# eMMC.net
KiCad netlist of a schematic drawn in Altium Designer
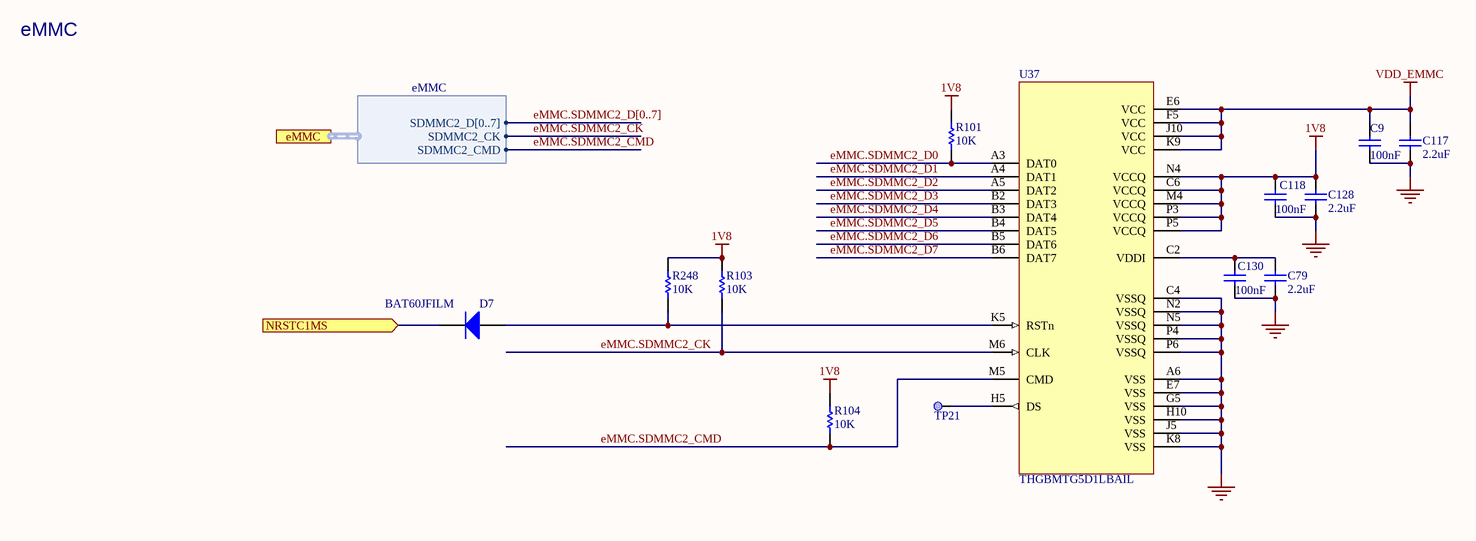
[diagram p0: eMMC.SchDoc]

(export (version "E")
  (design (tool "Eeschema 10.0.6"))
  (components
    (comp (ref "C9")
      (value "100nF")
      (footprint "C0402")
      (description "Capacitor, MLCC, 100nF, 16V, X7R, +/-10%, 0402, T=0.5mm")
      (fields (field (name "INTERNAL_PART_NUMBER") "MCD-00006") (field (name "MANUFACTURER") "YAGEO"))
      (libsource (lib "MCD_PARTS_database") (part "Capacitor"))
    )
    (comp (ref "C79")
      (value "2.2uF")
      (footprint "C0402")
      (description "Capacitor, MLCC, 2.2uF, 6.3V, X5R, +/-10%, 0402, T=0.5mm")
      (fields (field (name "INTERNAL_PART_NUMBER") "MCD-02606") (field (name "MANUFACTURER") "YAGEO"))
      (libsource (lib "MCD_PARTS_database") (part "Capacitor"))
    )
    (comp (ref "C117")
      (value "2.2uF")
      (footprint "C0402")
      (description "Capacitor, MLCC, 2.2uF, 6.3V, X5R, +/-10%, 0402, T=0.5mm")
      (fields (field (name "INTERNAL_PART_NUMBER") "MCD-02606") (field (name "MANUFACTURER") "YAGEO"))
      (libsource (lib "MCD_PARTS_database") (part "Capacitor"))
    )
    (comp (ref "C118")
      (value "100nF")
      (footprint "C0402")
      (description "Capacitor, MLCC, 100nF, 16V, X7R, +/-10%, 0402, T=0.5mm")
      (fields (field (name "INTERNAL_PART_NUMBER") "MCD-00006") (field (name "MANUFACTURER") "YAGEO"))
      (libsource (lib "MCD_PARTS_database") (part "Capacitor"))
    )
    (comp (ref "C128")
      (value "2.2uF")
      (footprint "C0402")
      (description "Capacitor, MLCC, 2.2uF, 6.3V, X5R, +/-10%, 0402, T=0.5mm")
      (fields (field (name "INTERNAL_PART_NUMBER") "MCD-02606") (field (name "MANUFACTURER") "YAGEO"))
      (libsource (lib "MCD_PARTS_database") (part "Capacitor"))
    )
    (comp (ref "C130")
      (value "100nF")
      (footprint "C0402")
      (description "Capacitor, MLCC, 100nF, 16V, X7R, +/-10%, 0402, T=0.5mm")
      (fields (field (name "INTERNAL_PART_NUMBER") "MCD-00006") (field (name "MANUFACTURER") "YAGEO"))
      (libsource (lib "MCD_PARTS_database") (part "Capacitor"))
    )
    (comp (ref "D7")
      (value "BAT60JFILM")
      (footprint "DIO_SOD323")
      (fields
        (field (name "INTERNAL_PART_NUMBER") "MCD-00034")
        (field (name "BMS_PART_NUMBER") "9151097")
        (field (name "MANUFACTURER") "STMICROELECTRONICS")
      )
      (libsource (lib "MCD_PARTS_database") (part "BAT60JFILM"))
    )
    (comp (ref "R101")
      (value "10K")
      (footprint "R0402")
      (description "Resistor,10K,0402,1%,1/16W")
      (fields
        (field (name "INTERNAL_PART_NUMBER") "MCD-00053")
        (field (name "MANUFACTURER_PART_NUMBER") "RC0402FR-0710KL")
        (field (name "PROVIDED_BY") "SUBCO")
      )
      (libsource (lib "MCD_PARTS_database") (part "Resistor"))
    )
    (comp (ref "R103")
      (value "10K")
      (footprint "R0402")
      (description "Resistor,10K,0402,1%,1/16W")
      (fields
        (field (name "INTERNAL_PART_NUMBER") "MCD-00053")
        (field (name "MANUFACTURER_PART_NUMBER") "RC0402FR-0710KL")
        (field (name "PROVIDED_BY") "SUBCO")
      )
      (libsource (lib "MCD_PARTS_database") (part "Resistor"))
    )
    (comp (ref "R104")
      (value "10K")
      (footprint "R0402")
      (description "Resistor,10K,0402,1%,1/16W")
      (fields
        (field (name "INTERNAL_PART_NUMBER") "MCD-00053")
        (field (name "MANUFACTURER_PART_NUMBER") "RC0402FR-0710KL")
        (field (name "PROVIDED_BY") "SUBCO")
      )
      (libsource (lib "MCD_PARTS_database") (part "Resistor"))
    )
    (comp (ref "R248")
      (value "10K")
      (footprint "R0402")
      (description "Resistor,10K,0402,1%,1/16W")
      (fields
        (field (name "INTERNAL_PART_NUMBER") "MCD-00053")
        (field (name "MANUFACTURER_PART_NUMBER") "RC0402FR-0710KL")
        (field (name "PROVIDED_BY") "SUBCO")
      )
      (libsource (lib "MCD_PARTS_database") (part "Resistor"))
    )
    (comp (ref "TP21")
      (value "Test Point")
      (footprint "TP_SMD_1MM")
      (description "Test Point 1mm")
      (fields
        (field (name "INTERNAL_PART_NUMBER") "MCD-00074")
        (field (name "MANUFACTURER_PART_NUMBER") "n/a")
      )
      (libsource (lib "MCD_PARTS_database") (part "Test Point"))
    )
    (comp (ref "U37")
      (value "THGBMTG5D1LBAIL")
      (footprint "ICC_P-WFBGA153_13X11P5_P050")
      (description "Memory, eMMC, 4GB, 15nm ,WFBGA , 153 pins")
      (fields (field (name "INTERNAL_PART_NUMBER") "MCD-02799") (field (name "MANUFACTURER") "KIOXIA"))
      (libsource (lib "MCD_PARTS_database") (part "eMMC_THGBMTG5D1LBAIL"))
    )
  )
  (nets
    (net (code "2") (name "/NRSTC1MS") (class "Default")
      (node (ref "D7") (pin "2") (pinfunction "K_2") (pintype "passive"))
    )
    (net (code "3") (name "/eMMC.SDMMC2_CK") (class "Default")
      (node (ref "R103") (pin "1") (pinfunction "1_1") (pintype "passive"))
      (node (ref "U37") (pin "M6") (pinfunction "CLK_M6") (pintype "input"))
    )
    (net (code "4") (name "/eMMC.SDMMC2_CMD") (class "Default")
      (node (ref "R104") (pin "1") (pinfunction "1_1") (pintype "passive"))
      (node (ref "U37") (pin "M5") (pinfunction "CMD_M5") (pintype "passive"))
    )
    (net (code "5") (name "/eMMC.SDMMC2_D0") (class "Default")
      (node (ref "R101") (pin "1") (pinfunction "1_1") (pintype "passive"))
      (node (ref "U37") (pin "A3") (pinfunction "DAT0_A3") (pintype "passive"))
    )
    (net (code "6") (name "/eMMC.SDMMC2_D1") (class "Default")
      (node (ref "U37") (pin "A4") (pinfunction "DAT1_A4") (pintype "passive"))
    )
    (net (code "7") (name "/eMMC.SDMMC2_D2") (class "Default")
      (node (ref "U37") (pin "A5") (pinfunction "DAT2_A5") (pintype "passive"))
    )
    (net (code "8") (name "/eMMC.SDMMC2_D3") (class "Default")
      (node (ref "U37") (pin "B2") (pinfunction "DAT3_B2") (pintype "passive"))
    )
    (net (code "9") (name "/eMMC.SDMMC2_D4") (class "Default")
      (node (ref "U37") (pin "B3") (pinfunction "DAT4_B3") (pintype "passive"))
    )
    (net (code "10") (name "/eMMC.SDMMC2_D5") (class "Default")
      (node (ref "U37") (pin "B4") (pinfunction "DAT5_B4") (pintype "passive"))
    )
    (net (code "11") (name "/eMMC.SDMMC2_D6") (class "Default")
      (node (ref "U37") (pin "B5") (pinfunction "DAT6_B5") (pintype "passive"))
    )
    (net (code "12") (name "/eMMC.SDMMC2_D7") (class "Default")
      (node (ref "U37") (pin "B6") (pinfunction "DAT7_B6") (pintype "passive"))
    )
    (net (code "15") (name "1V8") (class "Default")
      (node (ref "C118") (pin "2") (pinfunction "2_2") (pintype "passive"))
      (node (ref "C128") (pin "2") (pinfunction "2_2") (pintype "passive"))
      (node (ref "R101") (pin "2") (pinfunction "2_2") (pintype "passive"))
      (node (ref "R103") (pin "2") (pinfunction "2_2") (pintype "passive"))
      (node (ref "R104") (pin "2") (pinfunction "2_2") (pintype "passive"))
      (node (ref "R248") (pin "2") (pinfunction "2_2") (pintype "passive"))
      (node (ref "U37") (pin "C6") (pinfunction "VCCQ_C6") (pintype "passive"))
      (node (ref "U37") (pin "M4") (pinfunction "VCCQ_M4") (pintype "passive"))
      (node (ref "U37") (pin "N4") (pinfunction "VCCQ_N4") (pintype "passive"))
      (node (ref "U37") (pin "P3") (pinfunction "VCCQ_P3") (pintype "passive"))
      (node (ref "U37") (pin "P5") (pinfunction "VCCQ_P5") (pintype "passive"))
    )
    (net (code "16") (name "GND") (class "Default")
      (node (ref "C117") (pin "1") (pinfunction "1_1") (pintype "passive"))
      (node (ref "C118") (pin "1") (pinfunction "1_1") (pintype "passive"))
      (node (ref "C128") (pin "1") (pinfunction "1_1") (pintype "passive"))
      (node (ref "C130") (pin "1") (pinfunction "1_1") (pintype "passive"))
      (node (ref "C79") (pin "1") (pinfunction "1_1") (pintype "passive"))
      (node (ref "C9") (pin "1") (pinfunction "1_1") (pintype "passive"))
      (node (ref "U37") (pin "A6") (pinfunction "VSS_A6") (pintype "passive"))
      (node (ref "U37") (pin "C4") (pinfunction "VSSQ_C4") (pintype "passive"))
      (node (ref "U37") (pin "E7") (pinfunction "VSS_E7") (pintype "passive"))
      (node (ref "U37") (pin "G5") (pinfunction "VSS_G5") (pintype "passive"))
      (node (ref "U37") (pin "H10") (pinfunction "VSS_H10") (pintype "passive"))
      (node (ref "U37") (pin "J5") (pinfunction "VSS_J5") (pintype "passive"))
      (node (ref "U37") (pin "K8") (pinfunction "VSS_K8") (pintype "passive"))
      (node (ref "U37") (pin "N2") (pinfunction "VSSQ_N2") (pintype "passive"))
      (node (ref "U37") (pin "N5") (pinfunction "VSSQ_N5") (pintype "passive"))
      (node (ref "U37") (pin "P4") (pinfunction "VSSQ_P4") (pintype "passive"))
      (node (ref "U37") (pin "P6") (pinfunction "VSSQ_P6") (pintype "passive"))
    )
    (net (code "17") (name "Net-(D7-A)") (class "Default")
      (node (ref "D7") (pin "1") (pinfunction "A_1") (pintype "passive"))
      (node (ref "R248") (pin "1") (pinfunction "1_1") (pintype "passive"))
      (node (ref "U37") (pin "K5") (pinfunction "RSTn_K5") (pintype "input"))
    )
    (net (code "18") (name "Net-(U37-DS)") (class "Default")
      (node (ref "TP21") (pin "1") (pinfunction "1_1") (pintype "passive"))
      (node (ref "U37") (pin "H5") (pinfunction "DS_H5") (pintype "output"))
    )
    (net (code "19") (name "Net-(U37-VDDI)") (class "Default")
      (node (ref "C130") (pin "2") (pinfunction "2_2") (pintype "passive"))
      (node (ref "C79") (pin "2") (pinfunction "2_2") (pintype "passive"))
      (node (ref "U37") (pin "C2") (pinfunction "VDDI_C2") (pintype "passive"))
    )
    (net (code "20") (name "VDD_EMMC") (class "Default")
      (node (ref "C117") (pin "2") (pinfunction "2_2") (pintype "passive"))
      (node (ref "C9") (pin "2") (pinfunction "2_2") (pintype "passive"))
      (node (ref "U37") (pin "E6") (pinfunction "VCC_E6") (pintype "passive"))
      (node (ref "U37") (pin "F5") (pinfunction "VCC_F5") (pintype "passive"))
      (node (ref "U37") (pin "J10") (pinfunction "VCC_J10") (pintype "passive"))
      (node (ref "U37") (pin "K9") (pinfunction "VCC_K9") (pintype "passive"))
    )
  )
)
